# lumy.net
KiCad netlist of a schematic drawn in EAGLE
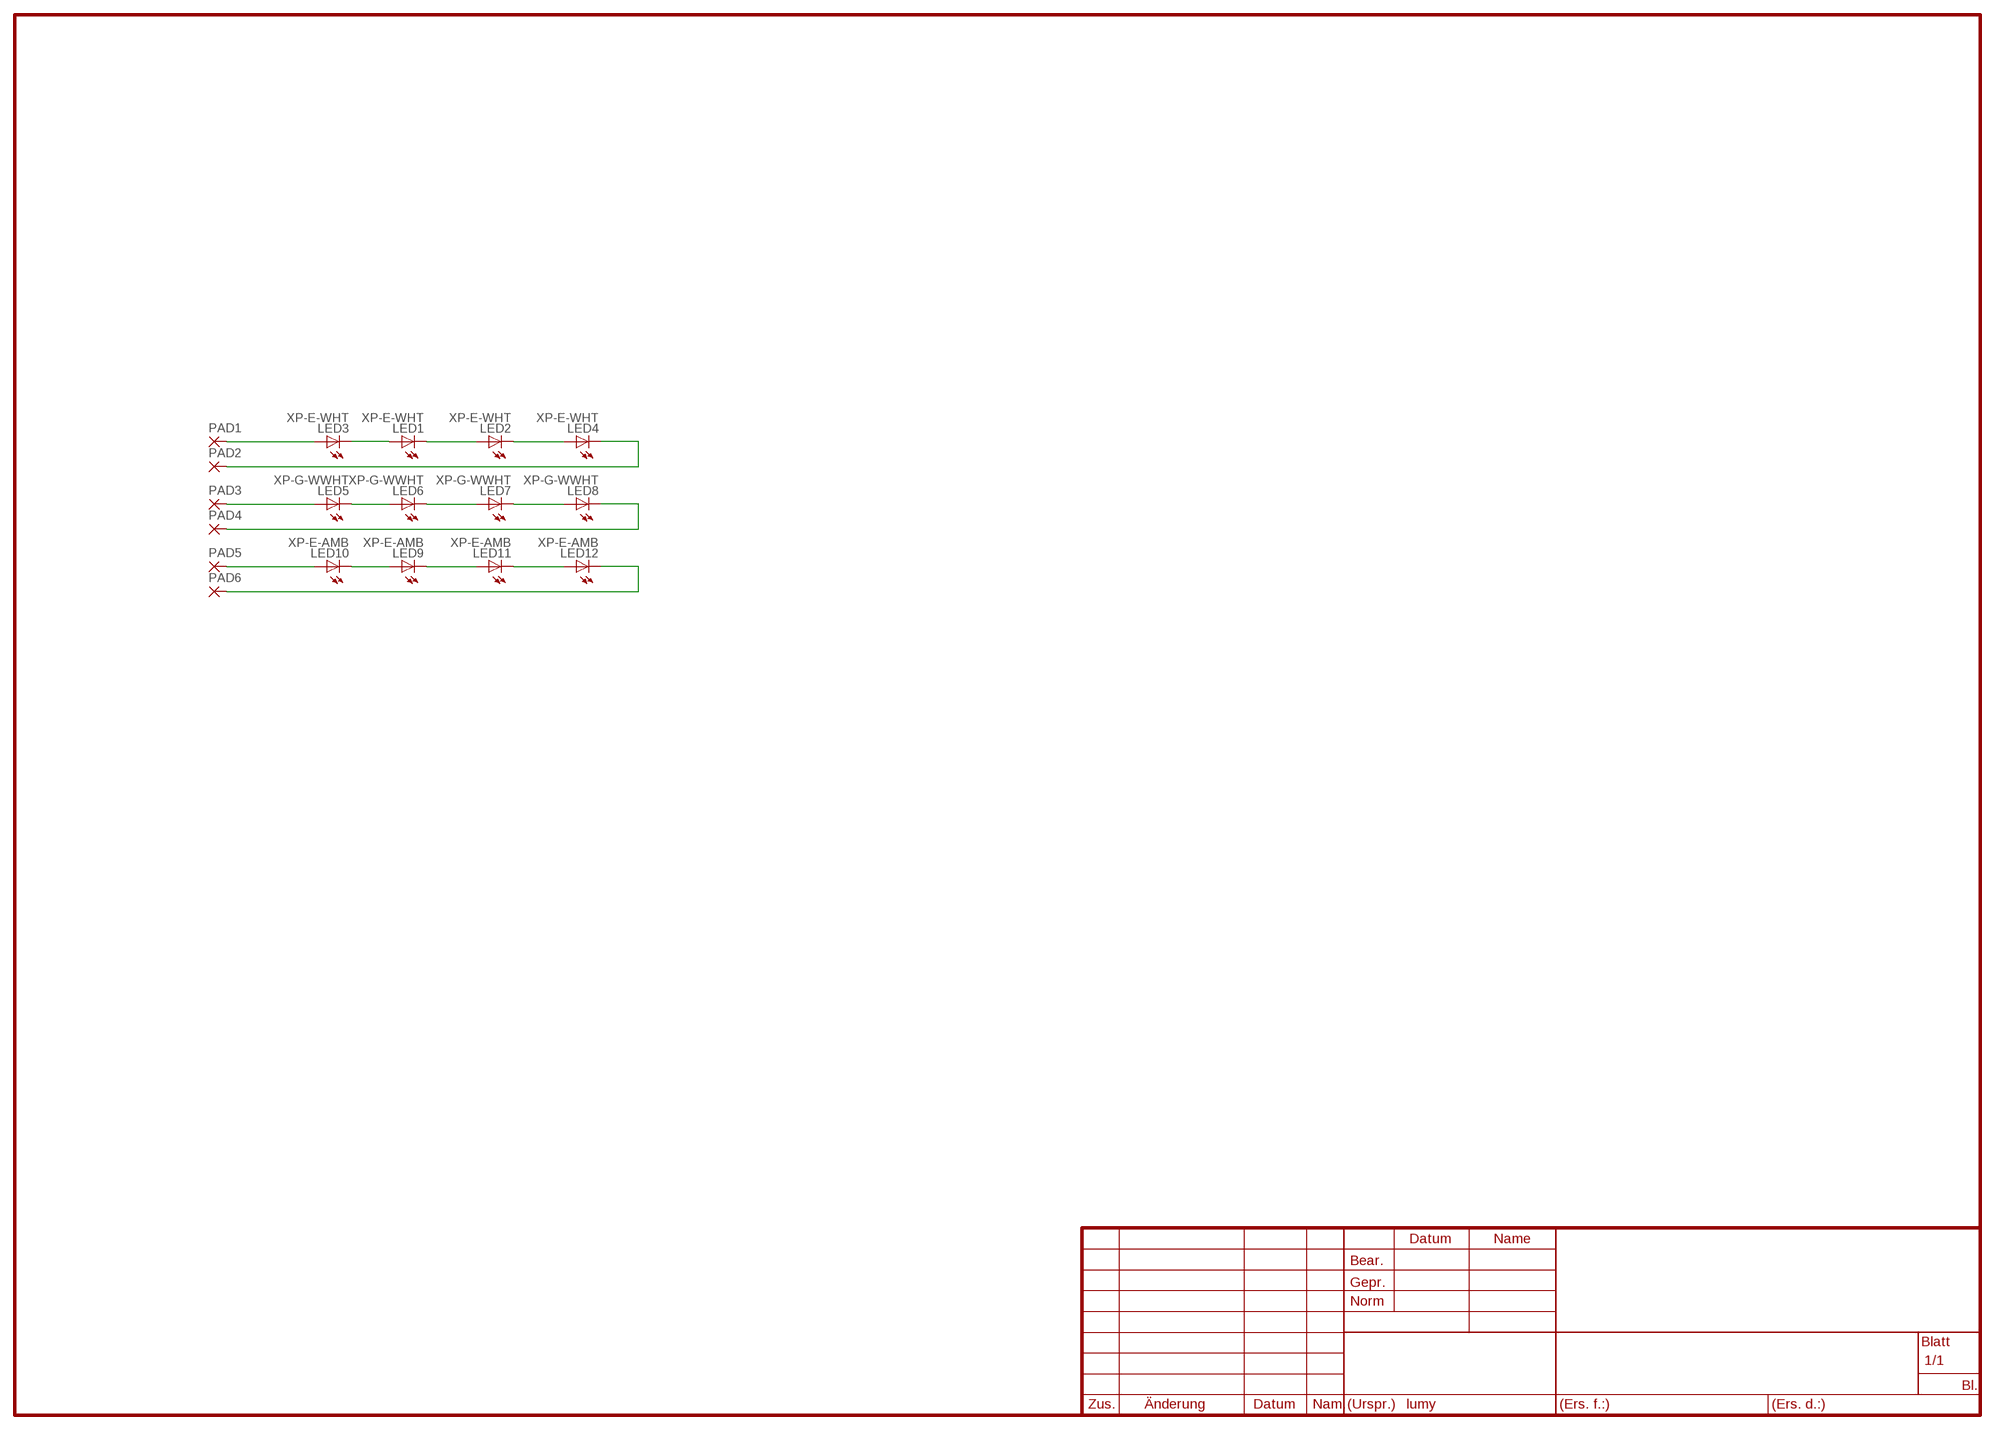
[diagram p0: schematic, sheet 1]

(export (version "E")
  (design (tool "Eeschema 10.0.6"))
  (components
    (comp (ref "LED1")
      (value "XP-E-WHT")
      (footprint "eagle-import:CREE_XLAMP")
      (libsource (lib "eagle-import") (part "XPEWHT-01-0000-00BC2"))
    )
    (comp (ref "LED2")
      (value "XP-E-WHT")
      (footprint "eagle-import:CREE_XLAMP")
      (libsource (lib "eagle-import") (part "XPEWHT-01-0000-00BC2"))
    )
    (comp (ref "LED3")
      (value "XP-E-WHT")
      (footprint "eagle-import:CREE_XLAMP")
      (libsource (lib "eagle-import") (part "XPEWHT-01-0000-00BC2"))
    )
    (comp (ref "LED4")
      (value "XP-E-WHT")
      (footprint "eagle-import:CREE_XLAMP")
      (libsource (lib "eagle-import") (part "XPEWHT-01-0000-00BC2"))
    )
    (comp (ref "LED5")
      (value "XP-G-WWHT")
      (footprint "eagle-import:CREE_XLAMP")
      (libsource (lib "eagle-import") (part "XPEWHT-01-0000-00BC2"))
    )
    (comp (ref "LED6")
      (value "XP-G-WWHT")
      (footprint "eagle-import:CREE_XLAMP")
      (libsource (lib "eagle-import") (part "XPEWHT-01-0000-00BC2"))
    )
    (comp (ref "LED7")
      (value "XP-G-WWHT")
      (footprint "eagle-import:CREE_XLAMP")
      (libsource (lib "eagle-import") (part "XPEWHT-01-0000-00BC2"))
    )
    (comp (ref "LED8")
      (value "XP-G-WWHT")
      (footprint "eagle-import:CREE_XLAMP")
      (libsource (lib "eagle-import") (part "XPEWHT-01-0000-00BC2"))
    )
    (comp (ref "LED9")
      (value "XP-E-AMB")
      (footprint "eagle-import:CREE_XLAMP")
      (libsource (lib "eagle-import") (part "XPEWHT-01-0000-00BC2"))
    )
    (comp (ref "LED10")
      (value "XP-E-AMB")
      (footprint "eagle-import:CREE_XLAMP")
      (libsource (lib "eagle-import") (part "XPEWHT-01-0000-00BC2"))
    )
    (comp (ref "LED11")
      (value "XP-E-AMB")
      (footprint "eagle-import:CREE_XLAMP")
      (libsource (lib "eagle-import") (part "XPEWHT-01-0000-00BC2"))
    )
    (comp (ref "LED12")
      (value "XP-E-AMB")
      (footprint "eagle-import:CREE_XLAMP")
      (libsource (lib "eagle-import") (part "XPEWHT-01-0000-00BC2"))
    )
    (comp (ref "PAD1")
      (value "SMD2")
      (footprint "eagle-import:SMD1,27-2,54")
      (libsource (lib "eagle-import") (part "SMD2"))
    )
    (comp (ref "PAD2")
      (value "SMD2")
      (footprint "eagle-import:SMD1,27-2,54")
      (libsource (lib "eagle-import") (part "SMD2"))
    )
    (comp (ref "PAD3")
      (value "SMD2")
      (footprint "eagle-import:SMD1,27-2,54")
      (libsource (lib "eagle-import") (part "SMD2"))
    )
    (comp (ref "PAD4")
      (value "SMD2")
      (footprint "eagle-import:SMD1,27-2,54")
      (libsource (lib "eagle-import") (part "SMD2"))
    )
    (comp (ref "PAD5")
      (value "SMD2")
      (footprint "eagle-import:SMD1,27-2,54")
      (libsource (lib "eagle-import") (part "SMD2"))
    )
    (comp (ref "PAD6")
      (value "SMD2")
      (footprint "eagle-import:SMD1,27-2,54")
      (libsource (lib "eagle-import") (part "SMD2"))
    )
  )
  (nets
    (net (code "1") (name "Net-(LED1-A-PadA@1)") (class "Default")
      (node (ref "LED1") (pin "A") (pinfunction "A_A") (pintype "passive"))
      (node (ref "LED1") (pin "A@1") (pinfunction "A_A@1") (pintype "passive"))
      (node (ref "LED3") (pin "C") (pinfunction "C_C") (pintype "passive"))
      (node (ref "LED3") (pin "C@1") (pinfunction "C_C@1") (pintype "passive"))
    )
    (net (code "2") (name "Net-(LED1-C-PadC@1)") (class "Default")
      (node (ref "LED1") (pin "C") (pinfunction "C_C") (pintype "passive"))
      (node (ref "LED1") (pin "C@1") (pinfunction "C_C@1") (pintype "passive"))
      (node (ref "LED2") (pin "A") (pinfunction "A_A") (pintype "passive"))
      (node (ref "LED2") (pin "A@1") (pinfunction "A_A@1") (pintype "passive"))
    )
    (net (code "3") (name "Net-(LED2-C-PadC@1)") (class "Default")
      (node (ref "LED2") (pin "C") (pinfunction "C_C") (pintype "passive"))
      (node (ref "LED2") (pin "C@1") (pinfunction "C_C@1") (pintype "passive"))
      (node (ref "LED4") (pin "A") (pinfunction "A_A") (pintype "passive"))
      (node (ref "LED4") (pin "A@1") (pinfunction "A_A@1") (pintype "passive"))
    )
    (net (code "4") (name "Net-(LED5-C-PadC@1)") (class "Default")
      (node (ref "LED5") (pin "C") (pinfunction "C_C") (pintype "passive"))
      (node (ref "LED5") (pin "C@1") (pinfunction "C_C@1") (pintype "passive"))
      (node (ref "LED6") (pin "A") (pinfunction "A_A") (pintype "passive"))
      (node (ref "LED6") (pin "A@1") (pinfunction "A_A@1") (pintype "passive"))
    )
    (net (code "5") (name "Net-(LED6-C-PadC@1)") (class "Default")
      (node (ref "LED6") (pin "C") (pinfunction "C_C") (pintype "passive"))
      (node (ref "LED6") (pin "C@1") (pinfunction "C_C@1") (pintype "passive"))
      (node (ref "LED7") (pin "A") (pinfunction "A_A") (pintype "passive"))
      (node (ref "LED7") (pin "A@1") (pinfunction "A_A@1") (pintype "passive"))
    )
    (net (code "6") (name "Net-(LED7-C-PadC@1)") (class "Default")
      (node (ref "LED7") (pin "C") (pinfunction "C_C") (pintype "passive"))
      (node (ref "LED7") (pin "C@1") (pinfunction "C_C@1") (pintype "passive"))
      (node (ref "LED8") (pin "A") (pinfunction "A_A") (pintype "passive"))
      (node (ref "LED8") (pin "A@1") (pinfunction "A_A@1") (pintype "passive"))
    )
    (net (code "7") (name "Net-(LED10-C-PadC@1)") (class "Default")
      (node (ref "LED10") (pin "C") (pinfunction "C_C") (pintype "passive"))
      (node (ref "LED10") (pin "C@1") (pinfunction "C_C@1") (pintype "passive"))
      (node (ref "LED9") (pin "A") (pinfunction "A_A") (pintype "passive"))
      (node (ref "LED9") (pin "A@1") (pinfunction "A_A@1") (pintype "passive"))
    )
    (net (code "8") (name "Net-(LED11-A-PadA@1)") (class "Default")
      (node (ref "LED11") (pin "A") (pinfunction "A_A") (pintype "passive"))
      (node (ref "LED11") (pin "A@1") (pinfunction "A_A@1") (pintype "passive"))
      (node (ref "LED9") (pin "C") (pinfunction "C_C") (pintype "passive"))
      (node (ref "LED9") (pin "C@1") (pinfunction "C_C@1") (pintype "passive"))
    )
    (net (code "9") (name "Net-(LED11-C-PadC@1)") (class "Default")
      (node (ref "LED11") (pin "C") (pinfunction "C_C") (pintype "passive"))
      (node (ref "LED11") (pin "C@1") (pinfunction "C_C@1") (pintype "passive"))
      (node (ref "LED12") (pin "A") (pinfunction "A_A") (pintype "passive"))
      (node (ref "LED12") (pin "A@1") (pinfunction "A_A@1") (pintype "passive"))
    )
    (net (code "10") (name "Net-(PAD1-P)") (class "Default")
      (node (ref "LED3") (pin "A") (pinfunction "A_A") (pintype "passive"))
      (node (ref "LED3") (pin "A@1") (pinfunction "A_A@1") (pintype "passive"))
      (node (ref "PAD1") (pin "1") (pinfunction "P_1") (pintype "passive"))
    )
    (net (code "11") (name "Net-(PAD2-P)") (class "Default")
      (node (ref "LED4") (pin "C") (pinfunction "C_C") (pintype "passive"))
      (node (ref "LED4") (pin "C@1") (pinfunction "C_C@1") (pintype "passive"))
      (node (ref "PAD2") (pin "1") (pinfunction "P_1") (pintype "passive"))
    )
    (net (code "12") (name "Net-(PAD3-P)") (class "Default")
      (node (ref "LED5") (pin "A") (pinfunction "A_A") (pintype "passive"))
      (node (ref "LED5") (pin "A@1") (pinfunction "A_A@1") (pintype "passive"))
      (node (ref "PAD3") (pin "1") (pinfunction "P_1") (pintype "passive"))
    )
    (net (code "13") (name "Net-(PAD4-P)") (class "Default")
      (node (ref "LED8") (pin "C") (pinfunction "C_C") (pintype "passive"))
      (node (ref "LED8") (pin "C@1") (pinfunction "C_C@1") (pintype "passive"))
      (node (ref "PAD4") (pin "1") (pinfunction "P_1") (pintype "passive"))
    )
    (net (code "14") (name "Net-(PAD5-P)") (class "Default")
      (node (ref "LED10") (pin "A") (pinfunction "A_A") (pintype "passive"))
      (node (ref "LED10") (pin "A@1") (pinfunction "A_A@1") (pintype "passive"))
      (node (ref "PAD5") (pin "1") (pinfunction "P_1") (pintype "passive"))
    )
    (net (code "15") (name "Net-(PAD6-P)") (class "Default")
      (node (ref "LED12") (pin "C") (pinfunction "C_C") (pintype "passive"))
      (node (ref "LED12") (pin "C@1") (pinfunction "C_C@1") (pintype "passive"))
      (node (ref "PAD6") (pin "1") (pinfunction "P_1") (pintype "passive"))
    )
  )
)
